# AD_starter_alternator.net
KiCad netlist of a schematic drawn in Altium Designer
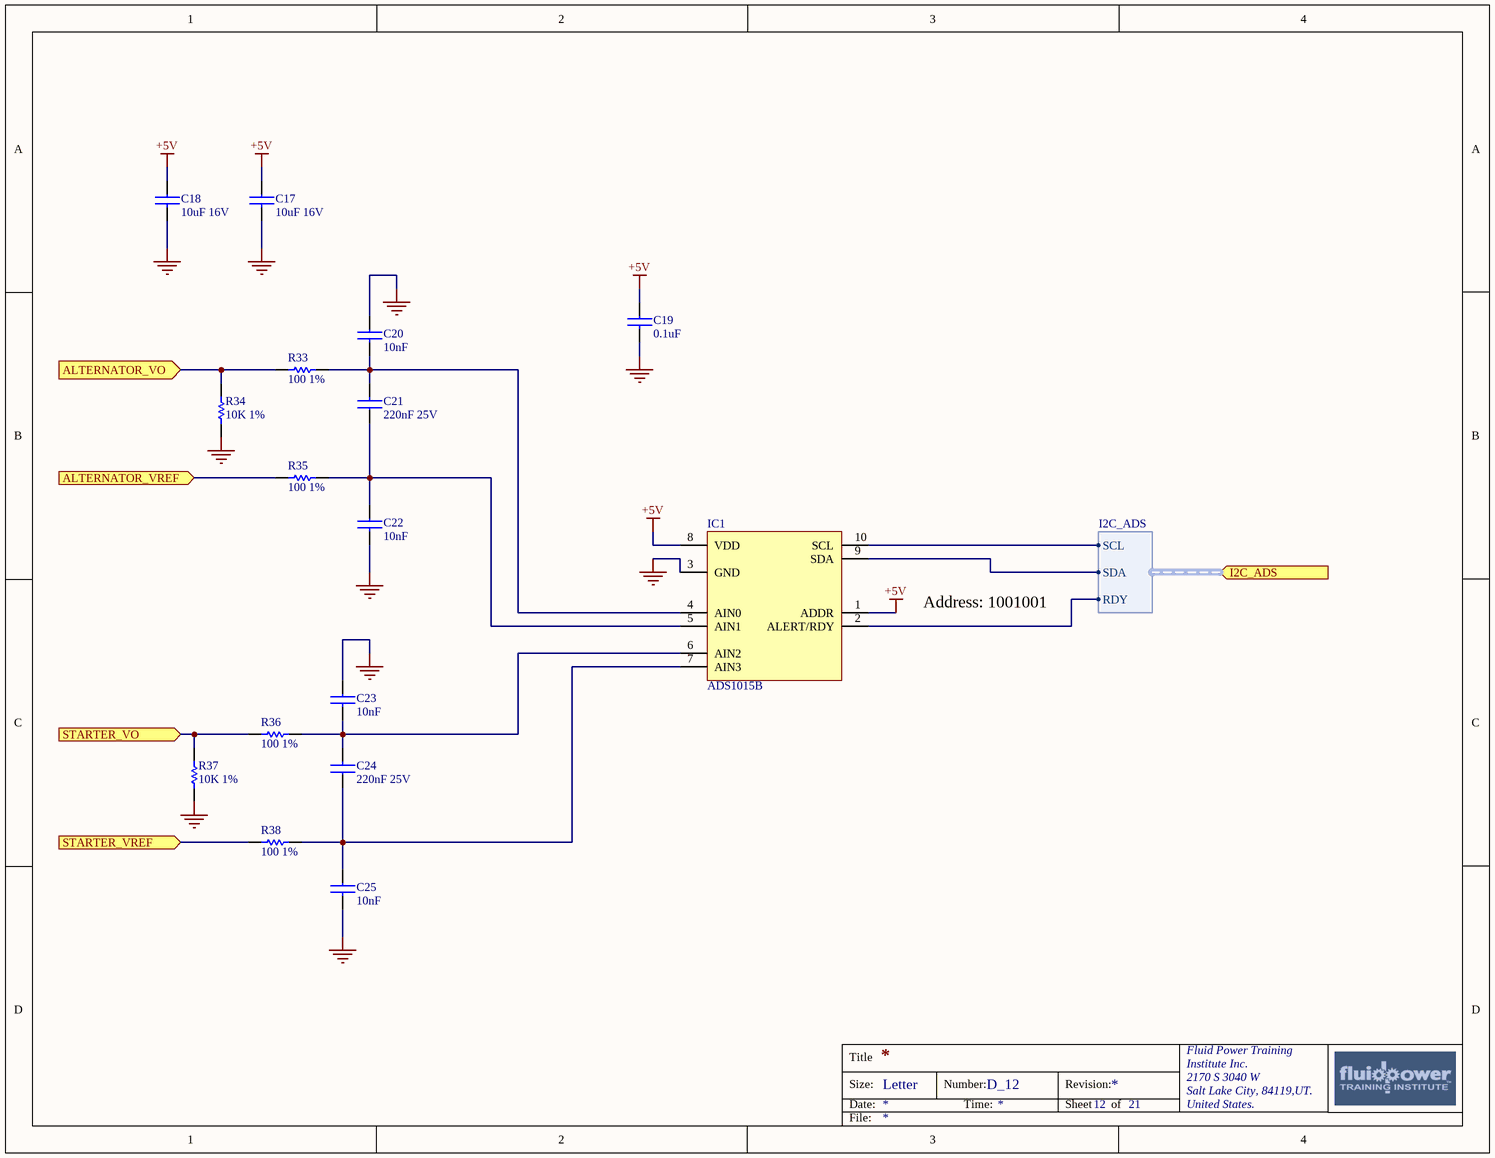
[diagram p0: AD_starter_alternator.SchDoc]

(export (version "E")
  (design (tool "Eeschema 10.0.6"))
  (components
    (comp (ref "C17")
      (value "10uF 16V")
      (footprint "C0805")
      (description "CAP CER 10UF 16V X5R 0805")
      (fields
        (field (name "MANUFACTURER") "Murata")
        (field (name "MANUFACTURER PART NUMBER") "GRM21BR61C106KE15L")
      )
      (libsource (lib "MCx") (part "GRM21BR61C106KE15L"))
    )
    (comp (ref "C18")
      (value "10uF 16V")
      (footprint "C0805")
      (description "CAP CER 10UF 16V X5R 0805")
      (fields
        (field (name "MANUFACTURER") "Murata")
        (field (name "MANUFACTURER PART NUMBER") "GRM21BR61C106KE15L")
      )
      (libsource (lib "MCx") (part "GRM21BR61C106KE15L"))
    )
    (comp (ref "C19")
      (value "0.1uF")
      (footprint "C0805")
      (description "Cap Ceramic 0.1uF 50V X7R 10% SMD 2.0 x 1.2 mm 125 C Paper T/R")
      (fields
        (field (name "MANUFACTURER") "KEMET")
        (field (name "MANUFACTURER PART NUMBER") "C0805C104K5RACTU")
      )
      (libsource (lib "MCx") (part "C0805C104K5RACTU"))
    )
    (comp (ref "C20")
      (value "10nF")
      (footprint "C0805")
      (fields
        (field (name "MANUFACTURER") "Yageo")
        (field (name "MANUFACTURER PART NUMBER") "CC0805KRX7R9BB103")
        (field (name "TOLERANCE") "10%")
      )
      (libsource (lib "MCx") (part "CC0805KRX7R9BB103"))
    )
    (comp (ref "C21")
      (value "220nF 25V")
      (footprint "C0805")
      (fields
        (field (name "MANUFACTURER") "Kyocera AVX")
        (field (name "MANUFACTURER PART NUMBER") "08053C224JAT2A")
        (field (name "TOLERANCE") "5%")
      )
      (libsource (lib "MCx") (part "08053C224JAT2A"))
    )
    (comp (ref "C22")
      (value "10nF")
      (footprint "C0805")
      (fields
        (field (name "MANUFACTURER") "Yageo")
        (field (name "MANUFACTURER PART NUMBER") "CC0805KRX7R9BB103")
        (field (name "TOLERANCE") "10%")
      )
      (libsource (lib "MCx") (part "CC0805KRX7R9BB103"))
    )
    (comp (ref "C23")
      (value "10nF")
      (footprint "C0805")
      (fields
        (field (name "MANUFACTURER") "Yageo")
        (field (name "MANUFACTURER PART NUMBER") "CC0805KRX7R9BB103")
        (field (name "TOLERANCE") "10%")
      )
      (libsource (lib "MCx") (part "CC0805KRX7R9BB103"))
    )
    (comp (ref "C24")
      (value "220nF 25V")
      (footprint "C0805")
      (fields
        (field (name "MANUFACTURER") "Kyocera AVX")
        (field (name "MANUFACTURER PART NUMBER") "08053C224JAT2A")
        (field (name "TOLERANCE") "5%")
      )
      (libsource (lib "MCx") (part "08053C224JAT2A"))
    )
    (comp (ref "C25")
      (value "10nF")
      (footprint "C0805")
      (fields
        (field (name "MANUFACTURER") "Yageo")
        (field (name "MANUFACTURER PART NUMBER") "CC0805KRX7R9BB103")
        (field (name "TOLERANCE") "10%")
      )
      (libsource (lib "MCx") (part "CC0805KRX7R9BB103"))
    )
    (comp (ref "IC1")
      (value "ADS1015B")
      (footprint "SOP50P490X110-10N")
      (description "ADS1015B Automotive 12-Bit ADC")
      (fields
        (field (name "MANUFACTURER") "Texas Instruments")
        (field (name "MANUFACTURER PART NUMBER") "ADS1015BQDGSRQ1")
      )
      (libsource (lib "MCx") (part "ADS1015BQDGSRQ1"))
    )
    (comp (ref "R33")
      (value "100 1%")
      (footprint "R0805")
      (description "Res Thick Film 0805 100 Ohm 1% 0.125W(1/8W) ±100ppm/C Molded SMD Automotive Paper T/R")
      (fields
        (field (name "MANUFACTURER") "Vishay Dale")
        (field (name "MANUFACTURER PART NUMBER") "CRCW0805100RFKEA")
      )
      (libsource (lib "MCx") (part "CRCW0805100RFKEA"))
    )
    (comp (ref "R34")
      (value "10K 1%")
      (footprint "R0805")
      (fields
        (field (name "MANUFACTURER") "Vishay")
        (field (name "MANUFACTURER PART NUMBER") "CRCW080510K0FKEA")
        (field (name "TOLERANCE") "1%")
      )
      (libsource (lib "MCx") (part "CRCW080510K0FKEA"))
    )
    (comp (ref "R35")
      (value "100 1%")
      (footprint "R0805")
      (description "Res Thick Film 0805 100 Ohm 1% 0.125W(1/8W) ±100ppm/C Molded SMD Automotive Paper T/R")
      (fields
        (field (name "MANUFACTURER") "Vishay Dale")
        (field (name "MANUFACTURER PART NUMBER") "CRCW0805100RFKEA")
      )
      (libsource (lib "MCx") (part "CRCW0805100RFKEA"))
    )
    (comp (ref "R36")
      (value "100 1%")
      (footprint "R0805")
      (description "Res Thick Film 0805 100 Ohm 1% 0.125W(1/8W) ±100ppm/C Molded SMD Automotive Paper T/R")
      (fields
        (field (name "MANUFACTURER") "Vishay Dale")
        (field (name "MANUFACTURER PART NUMBER") "CRCW0805100RFKEA")
      )
      (libsource (lib "MCx") (part "CRCW0805100RFKEA"))
    )
    (comp (ref "R37")
      (value "10K 1%")
      (footprint "R0805")
      (fields
        (field (name "MANUFACTURER") "Vishay")
        (field (name "MANUFACTURER PART NUMBER") "CRCW080510K0FKEA")
        (field (name "TOLERANCE") "1%")
      )
      (libsource (lib "MCx") (part "CRCW080510K0FKEA"))
    )
    (comp (ref "R38")
      (value "100 1%")
      (footprint "R0805")
      (description "Res Thick Film 0805 100 Ohm 1% 0.125W(1/8W) ±100ppm/C Molded SMD Automotive Paper T/R")
      (fields
        (field (name "MANUFACTURER") "Vishay Dale")
        (field (name "MANUFACTURER PART NUMBER") "CRCW0805100RFKEA")
      )
      (libsource (lib "MCx") (part "CRCW0805100RFKEA"))
    )
  )
  (nets
    (net (code "2") (name "+5V") (class "Default")
      (node (ref "C17") (pin "1") (pinfunction "1_1") (pintype "passive"))
      (node (ref "C18") (pin "1") (pinfunction "1_1") (pintype "passive"))
      (node (ref "C19") (pin "1") (pinfunction "1_1") (pintype "passive"))
      (node (ref "IC1") (pin "1") (pinfunction "ADDR_1") (pintype "passive"))
      (node (ref "IC1") (pin "8") (pinfunction "VDD_8") (pintype "passive"))
    )
    (net (code "3") (name "/ALTERNATOR_VO") (class "Default")
      (node (ref "R33") (pin "1") (pinfunction "1_1") (pintype "passive"))
      (node (ref "R34") (pin "2") (pinfunction "2_2") (pintype "passive"))
    )
    (net (code "4") (name "/ALTERNATOR_VREF") (class "Default")
      (node (ref "R35") (pin "1") (pinfunction "1_1") (pintype "passive"))
    )
    (net (code "5") (name "/RDY") (class "Default")
      (node (ref "IC1") (pin "2") (pinfunction "ALERT/RDY_2") (pintype "passive"))
    )
    (net (code "6") (name "/SCL") (class "Default")
      (node (ref "IC1") (pin "10") (pinfunction "SCL_10") (pintype "passive"))
    )
    (net (code "7") (name "/SDA") (class "Default")
      (node (ref "IC1") (pin "9") (pinfunction "SDA_9") (pintype "passive"))
    )
    (net (code "8") (name "/STARTER_VO") (class "Default")
      (node (ref "R36") (pin "1") (pinfunction "1_1") (pintype "passive"))
      (node (ref "R37") (pin "2") (pinfunction "2_2") (pintype "passive"))
    )
    (net (code "9") (name "/STARTER_VREF") (class "Default")
      (node (ref "R38") (pin "1") (pinfunction "1_1") (pintype "passive"))
    )
    (net (code "11") (name "GND") (class "Default")
      (node (ref "C17") (pin "2") (pinfunction "2_2") (pintype "passive"))
      (node (ref "C18") (pin "2") (pinfunction "2_2") (pintype "passive"))
      (node (ref "C19") (pin "2") (pinfunction "2_2") (pintype "passive"))
      (node (ref "C20") (pin "1") (pinfunction "1_1") (pintype "passive"))
      (node (ref "C22") (pin "2") (pinfunction "2_2") (pintype "passive"))
      (node (ref "C23") (pin "1") (pinfunction "1_1") (pintype "passive"))
      (node (ref "C25") (pin "2") (pinfunction "2_2") (pintype "passive"))
      (node (ref "IC1") (pin "3") (pinfunction "GND_3") (pintype "passive"))
      (node (ref "R34") (pin "1") (pinfunction "1_1") (pintype "passive"))
      (node (ref "R37") (pin "1") (pinfunction "1_1") (pintype "passive"))
    )
    (net (code "12") (name "Net-(IC1-AIN0)") (class "Default")
      (node (ref "C20") (pin "2") (pinfunction "2_2") (pintype "passive"))
      (node (ref "C21") (pin "2") (pinfunction "2_2") (pintype "passive"))
      (node (ref "IC1") (pin "4") (pinfunction "AIN0_4") (pintype "passive"))
      (node (ref "R33") (pin "2") (pinfunction "2_2") (pintype "passive"))
    )
    (net (code "13") (name "Net-(IC1-AIN1)") (class "Default")
      (node (ref "C21") (pin "1") (pinfunction "1_1") (pintype "passive"))
      (node (ref "C22") (pin "1") (pinfunction "1_1") (pintype "passive"))
      (node (ref "IC1") (pin "5") (pinfunction "AIN1_5") (pintype "passive"))
      (node (ref "R35") (pin "2") (pinfunction "2_2") (pintype "passive"))
    )
    (net (code "14") (name "Net-(IC1-AIN2)") (class "Default")
      (node (ref "C23") (pin "2") (pinfunction "2_2") (pintype "passive"))
      (node (ref "C24") (pin "2") (pinfunction "2_2") (pintype "passive"))
      (node (ref "IC1") (pin "6") (pinfunction "AIN2_6") (pintype "passive"))
      (node (ref "R36") (pin "2") (pinfunction "2_2") (pintype "passive"))
    )
    (net (code "15") (name "Net-(IC1-AIN3)") (class "Default")
      (node (ref "C24") (pin "1") (pinfunction "1_1") (pintype "passive"))
      (node (ref "C25") (pin "1") (pinfunction "1_1") (pintype "passive"))
      (node (ref "IC1") (pin "7") (pinfunction "AIN3_7") (pintype "passive"))
      (node (ref "R38") (pin "2") (pinfunction "2_2") (pintype "passive"))
    )
  )
)
